# RAC-tracker.net
KiCad netlist of a schematic drawn in EAGLE
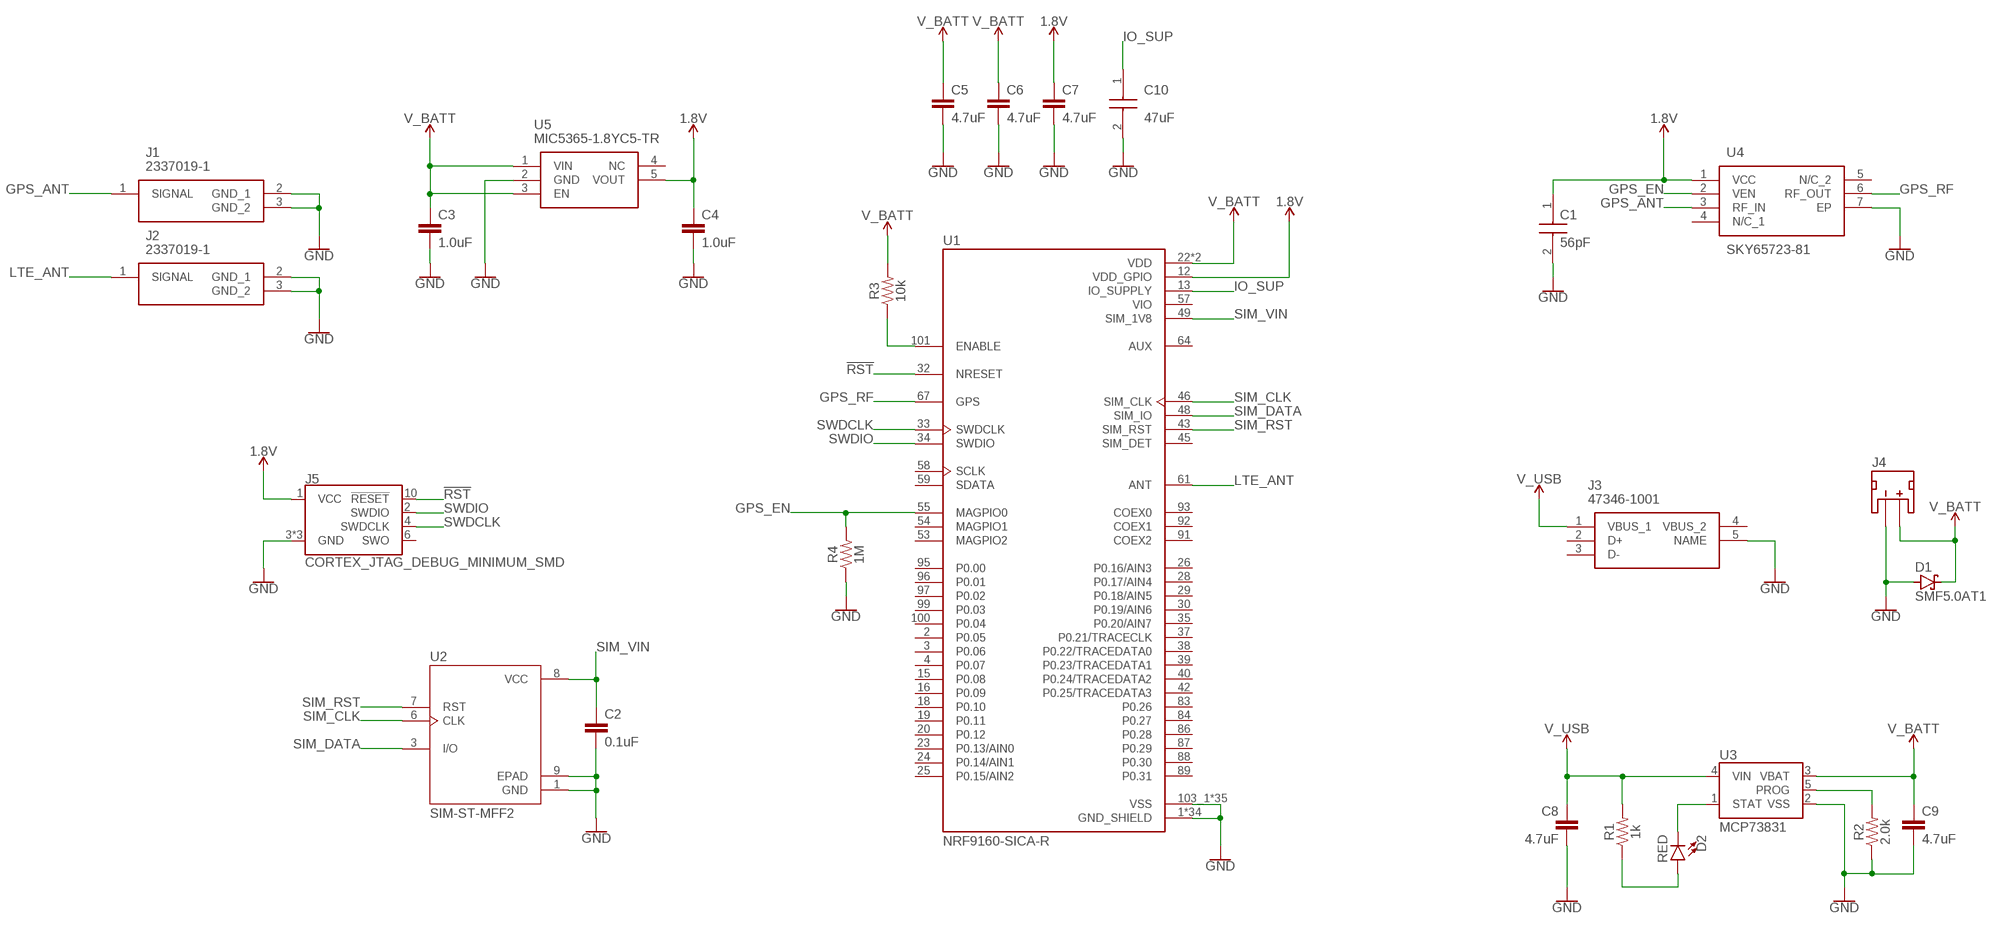
[diagram p0: schematic, sheet 1]

(export (version "E")
  (design (tool "Eeschema 10.0.6"))
  (components
    (comp (ref "C1")
      (value "56pF")
      (footprint "eagle-import:CAPC1608X90N")
      (fields
        (field (name "MANUFACTURER_PART_NUMBER") "GRM1885C1H560JA01J")
        (field (name "MOUSER_PART_NUMBER") "81-GRM39C560J50J")
      )
      (libsource (lib "eagle-import") (part "GRM1885C1H560JA01J"))
    )
    (comp (ref "C2")
      (value "0.1uF")
      (footprint "eagle-import:0603")
      (libsource (lib "eagle-import") (part "0.1UF-0603-25V-(+80/-20%)"))
    )
    (comp (ref "C3")
      (value "1.0uF")
      (footprint "eagle-import:0603")
      (libsource (lib "eagle-import") (part "1.0UF-0603-16V-10%"))
    )
    (comp (ref "C4")
      (value "1.0uF")
      (footprint "eagle-import:0603")
      (libsource (lib "eagle-import") (part "1.0UF-0603-16V-10%"))
    )
    (comp (ref "C5")
      (value "4.7uF")
      (footprint "eagle-import:0603")
      (libsource (lib "eagle-import") (part "4.7UF0603"))
    )
    (comp (ref "C6")
      (value "4.7uF")
      (footprint "eagle-import:0603")
      (libsource (lib "eagle-import") (part "4.7UF0603"))
    )
    (comp (ref "C7")
      (value "4.7uF")
      (footprint "eagle-import:0603")
      (libsource (lib "eagle-import") (part "4.7UF0603"))
    )
    (comp (ref "C8")
      (value "4.7uF")
      (footprint "eagle-import:0603")
      (libsource (lib "eagle-import") (part "4.7UF0603"))
    )
    (comp (ref "C9")
      (value "4.7uF")
      (footprint "eagle-import:0603")
      (libsource (lib "eagle-import") (part "4.7UF0603"))
    )
    (comp (ref "C10")
      (value "47uF")
      (footprint "eagle-import:CAPC2012X145N")
      (fields
        (field (name "MANUFACTURER_PART_NUMBER") "JMK212BBJ476MG-T")
        (field (name "MOUSER_PART_NUMBER") "963-JMK212BBJ476MG-T")
      )
      (libsource (lib "eagle-import") (part "JMK212BBJ476MG-T"))
    )
    (comp (ref "D1")
      (value "SMF5.0AT1")
      (footprint "eagle-import:SOD123FL")
      (libsource (lib "eagle-import") (part "SMF5.0AT1"))
    )
    (comp (ref "D2")
      (value "RED")
      (footprint "eagle-import:LED-0603")
      (libsource (lib "eagle-import") (part "LED-RED0603"))
    )
    (comp (ref "J1")
      (value "2337019-1")
      (footprint "eagle-import:23370191")
      (fields (field (name "MOUSER_PART_NUMBER") "571-2337019-1"))
      (libsource (lib "eagle-import") (part "2337019-1"))
    )
    (comp (ref "J2")
      (value "2337019-1")
      (footprint "eagle-import:23370191")
      (fields (field (name "MOUSER_PART_NUMBER") "571-2337019-1"))
      (libsource (lib "eagle-import") (part "2337019-1"))
    )
    (comp (ref "J3")
      (value "47346-1001")
      (footprint "eagle-import:47346-0001")
      (fields (field (name "MOUSER_PART_NUMBER") "538-47346-1001"))
      (libsource (lib "eagle-import") (part "47346-1001"))
    )
    (comp (ref "J4")
      (value "JST_2MM_MALE")
      (footprint "eagle-import:JST-2-SMD")
      (libsource (lib "eagle-import") (part "JST_2MM_MALE"))
    )
    (comp (ref "J5")
      (value "CORTEX_JTAG_DEBUG_MINIMUM_SMD")
      (footprint "eagle-import:2X5-SMD-1.27MM")
      (libsource (lib "eagle-import") (part "CORTEX_JTAG_DEBUG_MINIMUM_SMD"))
    )
    (comp (ref "R1")
      (value "1k")
      (footprint "eagle-import:0603")
      (libsource (lib "eagle-import") (part "1KOHM-0603-1/10W-1%"))
    )
    (comp (ref "R2")
      (value "2.0k")
      (footprint "eagle-import:0603")
      (libsource (lib "eagle-import") (part "2.0KOHM-0603-1/10W-5%"))
    )
    (comp (ref "R3")
      (value "10k")
      (footprint "eagle-import:0603")
      (libsource (lib "eagle-import") (part "10KOHM-0603-1/10W-1%"))
    )
    (comp (ref "R4")
      (value "1M")
      (footprint "eagle-import:0603")
      (libsource (lib "eagle-import") (part "1MOHM-0603-1/4W-5%"))
    )
    (comp (ref "U1")
      (value "NRF9160-SICA-R")
      (footprint "eagle-import:NORDIC_NRF9160-SICA-R")
      (fields (field (name "MF") "Nordic Semiconductor"))
      (libsource (lib "eagle-import") (part "NRF9160-SICA-R"))
    )
    (comp (ref "U2")
      (value "SIM-ST-MFF2")
      (footprint "eagle-import:PSON127P500X600X82-9N")
      (fields (field (name "DIGI-KEY_PART_NUMBER") "1887-1002-1-ND") (field (name "MF") "Hologram, Inc."))
      (libsource (lib "eagle-import") (part "SIM-ST-MFF2"))
    )
    (comp (ref "U3")
      (value "MCP73831")
      (footprint "eagle-import:SOT23-5")
      (libsource (lib "eagle-import") (part "MCP73831"))
    )
    (comp (ref "U4")
      (value "SKY65723-81")
      (footprint "eagle-import:SKY6572381")
      (fields (field (name "MOUSER_PART_NUMBER") "873-SKY65723-81"))
      (libsource (lib "eagle-import") (part "SKY65723-81"))
    )
    (comp (ref "U5")
      (value "MIC5365-1.8YC5-TR")
      (footprint "eagle-import:SOT65P210X110-5N")
      (fields (field (name "MOUSER_PART_NUMBER") "998-MIC5365-1.8YC5TR"))
      (libsource (lib "eagle-import") (part "MIC5365-1.8YC5-TR"))
    )
  )
  (nets
    (net (code "1") (name "/GPS_ANT") (class "Default")
      (node (ref "J1") (pin "1") (pinfunction "SIGNAL_1") (pintype "bidirectional"))
      (node (ref "U4") (pin "3") (pinfunction "RF_IN_3") (pintype "bidirectional"))
    )
    (net (code "2") (name "/GPS_EN") (class "Default")
      (node (ref "R4") (pin "2") (pinfunction "2_2") (pintype "passive"))
      (node (ref "U1") (pin "55") (pinfunction "MAGPIO0_55") (pintype "bidirectional"))
      (node (ref "U4") (pin "2") (pinfunction "VEN_2") (pintype "bidirectional"))
    )
    (net (code "3") (name "/GPS_RF") (class "Default")
      (node (ref "U1") (pin "67") (pinfunction "GPS_67") (pintype "input"))
      (node (ref "U4") (pin "6") (pinfunction "RF_OUT_6") (pintype "bidirectional"))
    )
    (net (code "4") (name "/IO_SUP") (class "Default")
      (node (ref "C10") (pin "1") (pinfunction "1_1") (pintype "bidirectional"))
      (node (ref "U1") (pin "13") (pinfunction "IO_SUPPLY_13") (pintype "power_in"))
    )
    (net (code "5") (name "/LTE_ANT") (class "Default")
      (node (ref "J2") (pin "1") (pinfunction "SIGNAL_1") (pintype "bidirectional"))
      (node (ref "U1") (pin "61") (pinfunction "ANT_61") (pintype "bidirectional"))
    )
    (net (code "6") (name "/SIM_CLK") (class "Default")
      (node (ref "U1") (pin "46") (pinfunction "SIM_CLK_46") (pintype "bidirectional"))
      (node (ref "U2") (pin "6") (pinfunction "CLK_6") (pintype "input"))
    )
    (net (code "7") (name "/SIM_DATA") (class "Default")
      (node (ref "U1") (pin "48") (pinfunction "SIM_IO_48") (pintype "bidirectional"))
      (node (ref "U2") (pin "3") (pinfunction "I/O_3") (pintype "bidirectional"))
    )
    (net (code "8") (name "/SIM_RST") (class "Default")
      (node (ref "U1") (pin "43") (pinfunction "SIM_RST_43") (pintype "bidirectional"))
      (node (ref "U2") (pin "7") (pinfunction "RST_7") (pintype "input"))
    )
    (net (code "9") (name "/SIM_VIN") (class "Default")
      (node (ref "C2") (pin "1") (pinfunction "1_1") (pintype "passive"))
      (node (ref "U1") (pin "49") (pinfunction "SIM_1V8_49") (pintype "power_in"))
      (node (ref "U2") (pin "8") (pinfunction "VCC_8") (pintype "power_in"))
    )
    (net (code "10") (name "/SWDCLK") (class "Default")
      (node (ref "J5") (pin "4") (pinfunction "SWDCLK_4") (pintype "bidirectional"))
      (node (ref "U1") (pin "33") (pinfunction "SWDCLK_33") (pintype "input"))
    )
    (net (code "11") (name "/SWDIO") (class "Default")
      (node (ref "J5") (pin "2") (pinfunction "SWDIO_2") (pintype "bidirectional"))
      (node (ref "U1") (pin "34") (pinfunction "SWDIO_34") (pintype "bidirectional"))
    )
    (net (code "12") (name "/VIO") (class "Default")
      (node (ref "U1") (pin "57") (pinfunction "VIO_57") (pintype "power_in"))
    )
    (net (code "13") (name "/~{RST}") (class "Default")
      (node (ref "J5") (pin "10") (pinfunction "~{RESET}_10") (pintype "bidirectional"))
      (node (ref "U1") (pin "32") (pinfunction "NRESET_32") (pintype "input"))
    )
    (net (code "14") (name "1.8V") (class "Default")
      (node (ref "C1") (pin "1") (pinfunction "1_1") (pintype "bidirectional"))
      (node (ref "C4") (pin "1") (pinfunction "1_1") (pintype "passive"))
      (node (ref "C7") (pin "1") (pinfunction "1_1") (pintype "passive"))
      (node (ref "J5") (pin "1") (pinfunction "VCC_1") (pintype "bidirectional"))
      (node (ref "U1") (pin "12") (pinfunction "VDD_GPIO_12") (pintype "power_in"))
      (node (ref "U4") (pin "1") (pinfunction "VCC_1") (pintype "bidirectional"))
      (node (ref "U5") (pin "5") (pinfunction "VOUT_5") (pintype "bidirectional"))
    )
    (net (code "15") (name "GND") (class "Default")
      (node (ref "C1") (pin "2") (pinfunction "2_2") (pintype "bidirectional"))
      (node (ref "C10") (pin "2") (pinfunction "2_2") (pintype "bidirectional"))
      (node (ref "C2") (pin "2") (pinfunction "2_2") (pintype "passive"))
      (node (ref "C3") (pin "2") (pinfunction "2_2") (pintype "passive"))
      (node (ref "C4") (pin "2") (pinfunction "2_2") (pintype "passive"))
      (node (ref "C5") (pin "2") (pinfunction "2_2") (pintype "passive"))
      (node (ref "C6") (pin "2") (pinfunction "2_2") (pintype "passive"))
      (node (ref "C7") (pin "2") (pinfunction "2_2") (pintype "passive"))
      (node (ref "C8") (pin "2") (pinfunction "2_2") (pintype "passive"))
      (node (ref "C9") (pin "2") (pinfunction "2_2") (pintype "passive"))
      (node (ref "D1") (pin "A") (pinfunction "A_A") (pintype "passive"))
      (node (ref "J1") (pin "2") (pinfunction "GND_1_2") (pintype "bidirectional"))
      (node (ref "J1") (pin "3") (pinfunction "GND_2_3") (pintype "bidirectional"))
      (node (ref "J2") (pin "2") (pinfunction "GND_1_2") (pintype "bidirectional"))
      (node (ref "J2") (pin "3") (pinfunction "GND_2_3") (pintype "bidirectional"))
      (node (ref "J3") (pin "5") (pinfunction "NAME_5") (pintype "bidirectional"))
      (node (ref "J4") (pin "1") (pinfunction "-_1") (pintype "bidirectional"))
      (node (ref "J5") (pin "3") (pinfunction "GND_3") (pintype "bidirectional"))
      (node (ref "J5") (pin "5") (pinfunction "GND_5") (pintype "bidirectional"))
      (node (ref "J5") (pin "9") (pinfunction "GND_9") (pintype "bidirectional"))
      (node (ref "R2") (pin "1") (pinfunction "1_1") (pintype "passive"))
      (node (ref "R4") (pin "1") (pinfunction "1_1") (pintype "passive"))
      (node (ref "U1") (pin "1") (pinfunction "GND_SHIELD_1") (pintype "power_in"))
      (node (ref "U1") (pin "103_1") (pinfunction "VSS_103_1") (pintype "power_in"))
      (node (ref "U1") (pin "103_10") (pinfunction "VSS_103_10") (pintype "power_in"))
      (node (ref "U1") (pin "103_11") (pinfunction "VSS_103_11") (pintype "power_in"))
      (node (ref "U1") (pin "103_12") (pinfunction "VSS_103_12") (pintype "power_in"))
      (node (ref "U1") (pin "103_13") (pinfunction "VSS_103_13") (pintype "power_in"))
      (node (ref "U1") (pin "103_14") (pinfunction "VSS_103_14") (pintype "power_in"))
      (node (ref "U1") (pin "103_15") (pinfunction "VSS_103_15") (pintype "power_in"))
      (node (ref "U1") (pin "103_16") (pinfunction "VSS_103_16") (pintype "power_in"))
      (node (ref "U1") (pin "103_17") (pinfunction "VSS_103_17") (pintype "power_in"))
      (node (ref "U1") (pin "103_18") (pinfunction "VSS_103_18") (pintype "power_in"))
      (node (ref "U1") (pin "103_19") (pinfunction "VSS_103_19") (pintype "power_in"))
      (node (ref "U1") (pin "103_2") (pinfunction "VSS_103_2") (pintype "power_in"))
      (node (ref "U1") (pin "103_20") (pinfunction "VSS_103_20") (pintype "power_in"))
      (node (ref "U1") (pin "103_21") (pinfunction "VSS_103_21") (pintype "power_in"))
      (node (ref "U1") (pin "103_22") (pinfunction "VSS_103_22") (pintype "power_in"))
      (node (ref "U1") (pin "103_23") (pinfunction "VSS_103_23") (pintype "power_in"))
      (node (ref "U1") (pin "103_24") (pinfunction "VSS_103_24") (pintype "power_in"))
      (node (ref "U1") (pin "103_25") (pinfunction "VSS_103_25") (pintype "power_in"))
      (node (ref "U1") (pin "103_26") (pinfunction "VSS_103_26") (pintype "power_in"))
      (node (ref "U1") (pin "103_27") (pinfunction "VSS_103_27") (pintype "power_in"))
      (node (ref "U1") (pin "103_28") (pinfunction "VSS_103_28") (pintype "power_in"))
      (node (ref "U1") (pin "103_29") (pinfunction "VSS_103_29") (pintype "power_in"))
      (node (ref "U1") (pin "103_3") (pinfunction "VSS_103_3") (pintype "power_in"))
      (node (ref "U1") (pin "103_30") (pinfunction "VSS_103_30") (pintype "power_in"))
      (node (ref "U1") (pin "103_31") (pinfunction "VSS_103_31") (pintype "power_in"))
      (node (ref "U1") (pin "103_32") (pinfunction "VSS_103_32") (pintype "power_in"))
      (node (ref "U1") (pin "103_33") (pinfunction "VSS_103_33") (pintype "power_in"))
      (node (ref "U1") (pin "103_34") (pinfunction "VSS_103_34") (pintype "power_in"))
      (node (ref "U1") (pin "103_35") (pinfunction "VSS_103_35") (pintype "power_in"))
      (node (ref "U1") (pin "103_4") (pinfunction "VSS_103_4") (pintype "power_in"))
      (node (ref "U1") (pin "103_5") (pinfunction "VSS_103_5") (pintype "power_in"))
      (node (ref "U1") (pin "103_6") (pinfunction "VSS_103_6") (pintype "power_in"))
      (node (ref "U1") (pin "103_7") (pinfunction "VSS_103_7") (pintype "power_in"))
      (node (ref "U1") (pin "103_8") (pinfunction "VSS_103_8") (pintype "power_in"))
      (node (ref "U1") (pin "103_9") (pinfunction "VSS_103_9") (pintype "power_in"))
      (node (ref "U1") (pin "14") (pinfunction "GND_SHIELD_14") (pintype "power_in"))
      (node (ref "U1") (pin "17") (pinfunction "GND_SHIELD_17") (pintype "power_in"))
      (node (ref "U1") (pin "21") (pinfunction "GND_SHIELD_21") (pintype "power_in"))
      (node (ref "U1") (pin "27") (pinfunction "GND_SHIELD_27") (pintype "power_in"))
      (node (ref "U1") (pin "31") (pinfunction "GND_SHIELD_31") (pintype "power_in"))
      (node (ref "U1") (pin "36") (pinfunction "GND_SHIELD_36") (pintype "power_in"))
      (node (ref "U1") (pin "41") (pinfunction "GND_SHIELD_41") (pintype "power_in"))
      (node (ref "U1") (pin "44") (pinfunction "GND_SHIELD_44") (pintype "power_in"))
      (node (ref "U1") (pin "47") (pinfunction "GND_SHIELD_47") (pintype "power_in"))
      (node (ref "U1") (pin "5") (pinfunction "GND_SHIELD_5") (pintype "power_in"))
      (node (ref "U1") (pin "50") (pinfunction "GND_SHIELD_50") (pintype "power_in"))
      (node (ref "U1") (pin "52") (pinfunction "GND_SHIELD_52") (pintype "power_in"))
      (node (ref "U1") (pin "56") (pinfunction "GND_SHIELD_56") (pintype "power_in"))
      (node (ref "U1") (pin "60") (pinfunction "GND_SHIELD_60") (pintype "power_in"))
      (node (ref "U1") (pin "62") (pinfunction "GND_SHIELD_62") (pintype "power_in"))
      (node (ref "U1") (pin "63") (pinfunction "GND_SHIELD_63") (pintype "power_in"))
      (node (ref "U1") (pin "65") (pinfunction "GND_SHIELD_65") (pintype "power_in"))
      (node (ref "U1") (pin "66") (pinfunction "GND_SHIELD_66") (pintype "power_in"))
      (node (ref "U1") (pin "72") (pinfunction "GND_SHIELD_72") (pintype "power_in"))
      (node (ref "U1") (pin "74") (pinfunction "GND_SHIELD_74") (pintype "power_in"))
      (node (ref "U1") (pin "75") (pinfunction "GND_SHIELD_75") (pintype "power_in"))
      (node (ref "U1") (pin "76") (pinfunction "GND_SHIELD_76") (pintype "power_in"))
      (node (ref "U1") (pin "77") (pinfunction "GND_SHIELD_77") (pintype "power_in"))
      (node (ref "U1") (pin "78") (pinfunction "GND_SHIELD_78") (pintype "power_in"))
      (node (ref "U1") (pin "79") (pinfunction "GND_SHIELD_79") (pintype "power_in"))
      (node (ref "U1") (pin "80") (pinfunction "GND_SHIELD_80") (pintype "power_in"))
      (node (ref "U1") (pin "81") (pinfunction "GND_SHIELD_81") (pintype "power_in"))
      (node (ref "U1") (pin "82") (pinfunction "GND_SHIELD_82") (pintype "power_in"))
      (node (ref "U1") (pin "85") (pinfunction "GND_SHIELD_85") (pintype "power_in"))
      (node (ref "U1") (pin "9") (pinfunction "GND_SHIELD_9") (pintype "power_in"))
      (node (ref "U1") (pin "90") (pinfunction "GND_SHIELD_90") (pintype "power_in"))
      (node (ref "U1") (pin "94") (pinfunction "GND_SHIELD_94") (pintype "power_in"))
      (node (ref "U1") (pin "98") (pinfunction "GND_SHIELD_98") (pintype "power_in"))
      (node (ref "U2") (pin "1") (pinfunction "GND_1") (pintype "power_in"))
      (node (ref "U2") (pin "9") (pinfunction "EPAD_9") (pintype "passive"))
      (node (ref "U3") (pin "2") (pinfunction "VSS_2") (pintype "power_in"))
      (node (ref "U4") (pin "7") (pinfunction "EP_7") (pintype "bidirectional"))
      (node (ref "U5") (pin "2") (pinfunction "GND_2") (pintype "bidirectional"))
    )
    (net (code "16") (name "Net-(D2-PadA)") (class "Default")
      (node (ref "D2") (pin "A") (pinfunction "A_A") (pintype "passive"))
      (node (ref "R1") (pin "1") (pinfunction "1_1") (pintype "passive"))
    )
    (net (code "17") (name "Net-(U1-ENABLE)") (class "Default")
      (node (ref "R3") (pin "1") (pinfunction "1_1") (pintype "passive"))
      (node (ref "U1") (pin "101") (pinfunction "ENABLE_101") (pintype "input"))
    )
    (net (code "18") (name "Net-(U3-PROG)") (class "Default")
      (node (ref "R2") (pin "2") (pinfunction "2_2") (pintype "passive"))
      (node (ref "U3") (pin "5") (pinfunction "PROG_5") (pintype "input"))
    )
    (net (code "19") (name "Net-(U3-STAT)") (class "Default")
      (node (ref "D2") (pin "C") (pinfunction "C_C") (pintype "passive"))
      (node (ref "U3") (pin "1") (pinfunction "STAT_1") (pintype "output"))
    )
    (net (code "20") (name "V_BATT") (class "Default")
      (node (ref "C3") (pin "1") (pinfunction "1_1") (pintype "passive"))
      (node (ref "C5") (pin "1") (pinfunction "1_1") (pintype "passive"))
      (node (ref "C6") (pin "1") (pinfunction "1_1") (pintype "passive"))
      (node (ref "C9") (pin "1") (pinfunction "1_1") (pintype "passive"))
      (node (ref "D1") (pin "C") (pinfunction "C_C") (pintype "passive"))
      (node (ref "J4") (pin "2") (pinfunction "+_2") (pintype "bidirectional"))
      (node (ref "R3") (pin "2") (pinfunction "2_2") (pintype "passive"))
      (node (ref "U1") (pin "102") (pinfunction "VDD_102") (pintype "power_in"))
      (node (ref "U1") (pin "22") (pinfunction "VDD_22") (pintype "power_in"))
      (node (ref "U3") (pin "3") (pinfunction "VBAT_3") (pintype "power_in"))
      (node (ref "U5") (pin "1") (pinfunction "VIN_1") (pintype "bidirectional"))
      (node (ref "U5") (pin "3") (pinfunction "EN_3") (pintype "bidirectional"))
    )
    (net (code "21") (name "V_USB") (class "Default")
      (node (ref "C8") (pin "1") (pinfunction "1_1") (pintype "passive"))
      (node (ref "J3") (pin "1") (pinfunction "VBUS_1_1") (pintype "bidirectional"))
      (node (ref "R1") (pin "2") (pinfunction "2_2") (pintype "passive"))
      (node (ref "U3") (pin "4") (pinfunction "VIN_4") (pintype "power_in"))
    )
    (net (code "22") (name "unconnected-(J3-D+-Pad2)") (class "Default")
      (node (ref "J3") (pin "2") (pinfunction "D+_2") (pintype "bidirectional"))
    )
    (net (code "23") (name "unconnected-(J3-D--Pad3)") (class "Default")
      (node (ref "J3") (pin "3") (pinfunction "D-_3") (pintype "bidirectional"))
    )
    (net (code "24") (name "unconnected-(J3-VBUS_2-Pad4)") (class "Default")
      (node (ref "J3") (pin "4") (pinfunction "VBUS_2_4") (pintype "bidirectional"))
    )
    (net (code "25") (name "unconnected-(J4-PAD1-PadNC1)") (class "Default")
      (node (ref "J4") (pin "NC1") (pinfunction "PAD1_NC1") (pintype "bidirectional"))
    )
    (net (code "26") (name "unconnected-(J4-PAD2-PadNC2)") (class "Default")
      (node (ref "J4") (pin "NC2") (pinfunction "PAD2_NC2") (pintype "bidirectional"))
    )
    (net (code "27") (name "unconnected-(J5-SWO-Pad6)") (class "Default")
      (node (ref "J5") (pin "6") (pinfunction "SWO_6") (pintype "bidirectional"))
    )
    (net (code "28") (name "unconnected-(U1-AUX-Pad64)") (class "Default")
      (node (ref "U1") (pin "64") (pinfunction "AUX_64") (pintype "output"))
    )
    (net (code "29") (name "unconnected-(U1-COEX0-Pad93)") (class "Default")
      (node (ref "U1") (pin "93") (pinfunction "COEX0_93") (pintype "bidirectional"))
    )
    (net (code "30") (name "unconnected-(U1-COEX1-Pad92)") (class "Default")
      (node (ref "U1") (pin "92") (pinfunction "COEX1_92") (pintype "bidirectional"))
    )
    (net (code "31") (name "unconnected-(U1-COEX2-Pad91)") (class "Default")
      (node (ref "U1") (pin "91") (pinfunction "COEX2_91") (pintype "bidirectional"))
    )
    (net (code "32") (name "unconnected-(U1-MAGPIO1-Pad54)") (class "Default")
      (node (ref "U1") (pin "54") (pinfunction "MAGPIO1_54") (pintype "bidirectional"))
    )
    (net (code "33") (name "unconnected-(U1-MAGPIO2-Pad53)") (class "Default")
      (node (ref "U1") (pin "53") (pinfunction "MAGPIO2_53") (pintype "bidirectional"))
    )
    (net (code "34") (name "unconnected-(U1-P0.00-Pad95)") (class "Default")
      (node (ref "U1") (pin "95") (pinfunction "P0.00_95") (pintype "bidirectional"))
    )
    (net (code "35") (name "unconnected-(U1-P0.01-Pad96)") (class "Default")
      (node (ref "U1") (pin "96") (pinfunction "P0.01_96") (pintype "bidirectional"))
    )
    (net (code "36") (name "unconnected-(U1-P0.02-Pad97)") (class "Default")
      (node (ref "U1") (pin "97") (pinfunction "P0.02_97") (pintype "bidirectional"))
    )
    (net (code "37") (name "unconnected-(U1-P0.03-Pad99)") (class "Default")
      (node (ref "U1") (pin "99") (pinfunction "P0.03_99") (pintype "bidirectional"))
    )
    (net (code "38") (name "unconnected-(U1-P0.04-Pad100)") (class "Default")
      (node (ref "U1") (pin "100") (pinfunction "P0.04_100") (pintype "bidirectional"))
    )
    (net (code "39") (name "unconnected-(U1-P0.05-Pad2)") (class "Default")
      (node (ref "U1") (pin "2") (pinfunction "P0.05_2") (pintype "bidirectional"))
    )
    (net (code "40") (name "unconnected-(U1-P0.06-Pad3)") (class "Default")
      (node (ref "U1") (pin "3") (pinfunction "P0.06_3") (pintype "bidirectional"))
    )
    (net (code "41") (name "unconnected-(U1-P0.07-Pad4)") (class "Default")
      (node (ref "U1") (pin "4") (pinfunction "P0.07_4") (pintype "bidirectional"))
    )
    (net (code "42") (name "unconnected-(U1-P0.08-Pad15)") (class "Default")
      (node (ref "U1") (pin "15") (pinfunction "P0.08_15") (pintype "bidirectional"))
    )
    (net (code "43") (name "unconnected-(U1-P0.09-Pad16)") (class "Default")
      (node (ref "U1") (pin "16") (pinfunction "P0.09_16") (pintype "bidirectional"))
    )
    (net (code "44") (name "unconnected-(U1-P0.10-Pad18)") (class "Default")
      (node (ref "U1") (pin "18") (pinfunction "P0.10_18") (pintype "bidirectional"))
    )
    (net (code "45") (name "unconnected-(U1-P0.11-Pad19)") (class "Default")
      (node (ref "U1") (pin "19") (pinfunction "P0.11_19") (pintype "bidirectional"))
    )
    (net (code "46") (name "unconnected-(U1-P0.12-Pad20)") (class "Default")
      (node (ref "U1") (pin "20") (pinfunction "P0.12_20") (pintype "bidirectional"))
    )
    (net (code "47") (name "unconnected-(U1-P0.13{slash}AIN0-Pad23)") (class "Default")
      (node (ref "U1") (pin "23") (pinfunction "P0.13/AIN0_23") (pintype "bidirectional"))
    )
    (net (code "48") (name "unconnected-(U1-P0.14{slash}AIN1-Pad24)") (class "Default")
      (node (ref "U1") (pin "24") (pinfunction "P0.14/AIN1_24") (pintype "bidirectional"))
    )
    (net (code "49") (name "unconnected-(U1-P0.15{slash}AIN2-Pad25)") (class "Default")
      (node (ref "U1") (pin "25") (pinfunction "P0.15/AIN2_25") (pintype "bidirectional"))
    )
    (net (code "50") (name "unconnected-(U1-P0.16{slash}AIN3-Pad26)") (class "Default")
      (node (ref "U1") (pin "26") (pinfunction "P0.16/AIN3_26") (pintype "bidirectional"))
    )
    (net (code "51") (name "unconnected-(U1-P0.17{slash}AIN4-Pad28)") (class "Default")
      (node (ref "U1") (pin "28") (pinfunction "P0.17/AIN4_28") (pintype "bidirectional"))
    )
    (net (code "52") (name "unconnected-(U1-P0.18{slash}AIN5-Pad29)") (class "Default")
      (node (ref "U1") (pin "29") (pinfunction "P0.18/AIN5_29") (pintype "bidirectional"))
    )
    (net (code "53") (name "unconnected-(U1-P0.19{slash}AIN6-Pad30)") (class "Default")
      (node (ref "U1") (pin "30") (pinfunction "P0.19/AIN6_30") (pintype "bidirectional"))
    )
    (net (code "54") (name "unconnected-(U1-P0.20{slash}AIN7-Pad35)") (class "Default")
      (node (ref "U1") (pin "35") (pinfunction "P0.20/AIN7_35") (pintype "bidirectional"))
    )
    (net (code "55") (name "unconnected-(U1-P0.21{slash}TRACECLK-Pad37)") (class "Default")
      (node (ref "U1") (pin "37") (pinfunction "P0.21/TRACECLK_37") (pintype "bidirectional"))
    )
    (net (code "56") (name "unconnected-(U1-P0.22{slash}TRACEDATA0-Pad38)") (class "Default")
      (node (ref "U1") (pin "38") (pinfunction "P0.22/TRACEDATA0_38") (pintype "bidirectional"))
    )
    (net (code "57") (name "unconnected-(U1-P0.23{slash}TRACEDATA1-Pad39)") (class "Default")
      (node (ref "U1") (pin "39") (pinfunction "P0.23/TRACEDATA1_39") (pintype "bidirectional"))
    )
    (net (code "58") (name "unconnected-(U1-P0.24{slash}TRACEDATA2-Pad40)") (class "Default")
      (node (ref "U1") (pin "40") (pinfunction "P0.24/TRACEDATA2_40") (pintype "bidirectional"))
    )
    (net (code "59") (name "unconnected-(U1-P0.25{slash}TRACEDATA3-Pad42)") (class "Default")
      (node (ref "U1") (pin "42") (pinfunction "P0.25/TRACEDATA3_42") (pintype "bidirectional"))
    )
    (net (code "60") (name "unconnected-(U1-P0.26-Pad83)") (class "Default")
      (node (ref "U1") (pin "83") (pinfunction "P0.26_83") (pintype "bidirectional"))
    )
    (net (code "61") (name "unconnected-(U1-P0.27-Pad84)") (class "Default")
      (node (ref "U1") (pin "84") (pinfunction "P0.27_84") (pintype "bidirectional"))
    )
    (net (code "62") (name "unconnected-(U1-P0.28-Pad86)") (class "Default")
      (node (ref "U1") (pin "86") (pinfunction "P0.28_86") (pintype "bidirectional"))
    )
    (net (code "63") (name "unconnected-(U1-P0.29-Pad87)") (class "Default")
      (node (ref "U1") (pin "87") (pinfunction "P0.29_87") (pintype "bidirectional"))
    )
    (net (code "64") (name "unconnected-(U1-P0.30-Pad88)") (class "Default")
      (node (ref "U1") (pin "88") (pinfunction "P0.30_88") (pintype "bidirectional"))
    )
    (net (code "65") (name "unconnected-(U1-P0.31-Pad89)") (class "Default")
      (node (ref "U1") (pin "89") (pinfunction "P0.31_89") (pintype "bidirectional"))
    )
    (net (code "66") (name "unconnected-(U1-SCLK-Pad58)") (class "Default")
      (node (ref "U1") (pin "58") (pinfunction "SCLK_58") (pintype "bidirectional"))
    )
    (net (code "67") (name "unconnected-(U1-SDATA-Pad59)") (class "Default")
      (node (ref "U1") (pin "59") (pinfunction "SDATA_59") (pintype "bidirectional"))
    )
    (net (code "68") (name "unconnected-(U1-SIM_DET-Pad45)") (class "Default")
      (node (ref "U1") (pin "45") (pinfunction "SIM_DET_45") (pintype "bidirectional"))
    )
    (net (code "69") (name "unconnected-(U4-N{slash}C_1-Pad4)") (class "Default")
      (node (ref "U4") (pin "4") (pinfunction "N/C_1_4") (pintype "bidirectional"))
    )
    (net (code "70") (name "unconnected-(U4-N{slash}C_2-Pad5)") (class "Default")
      (node (ref "U4") (pin "5") (pinfunction "N/C_2_5") (pintype "bidirectional"))
    )
    (net (code "71") (name "unconnected-(U5-NC-Pad4)") (class "Default")
      (node (ref "U5") (pin "4") (pinfunction "NC_4") (pintype "no_connect"))
    )
  )
)
